# SCH_POC-HC-05_2022-12-13.net
KiCad netlist of a schematic drawn in EasyEDA
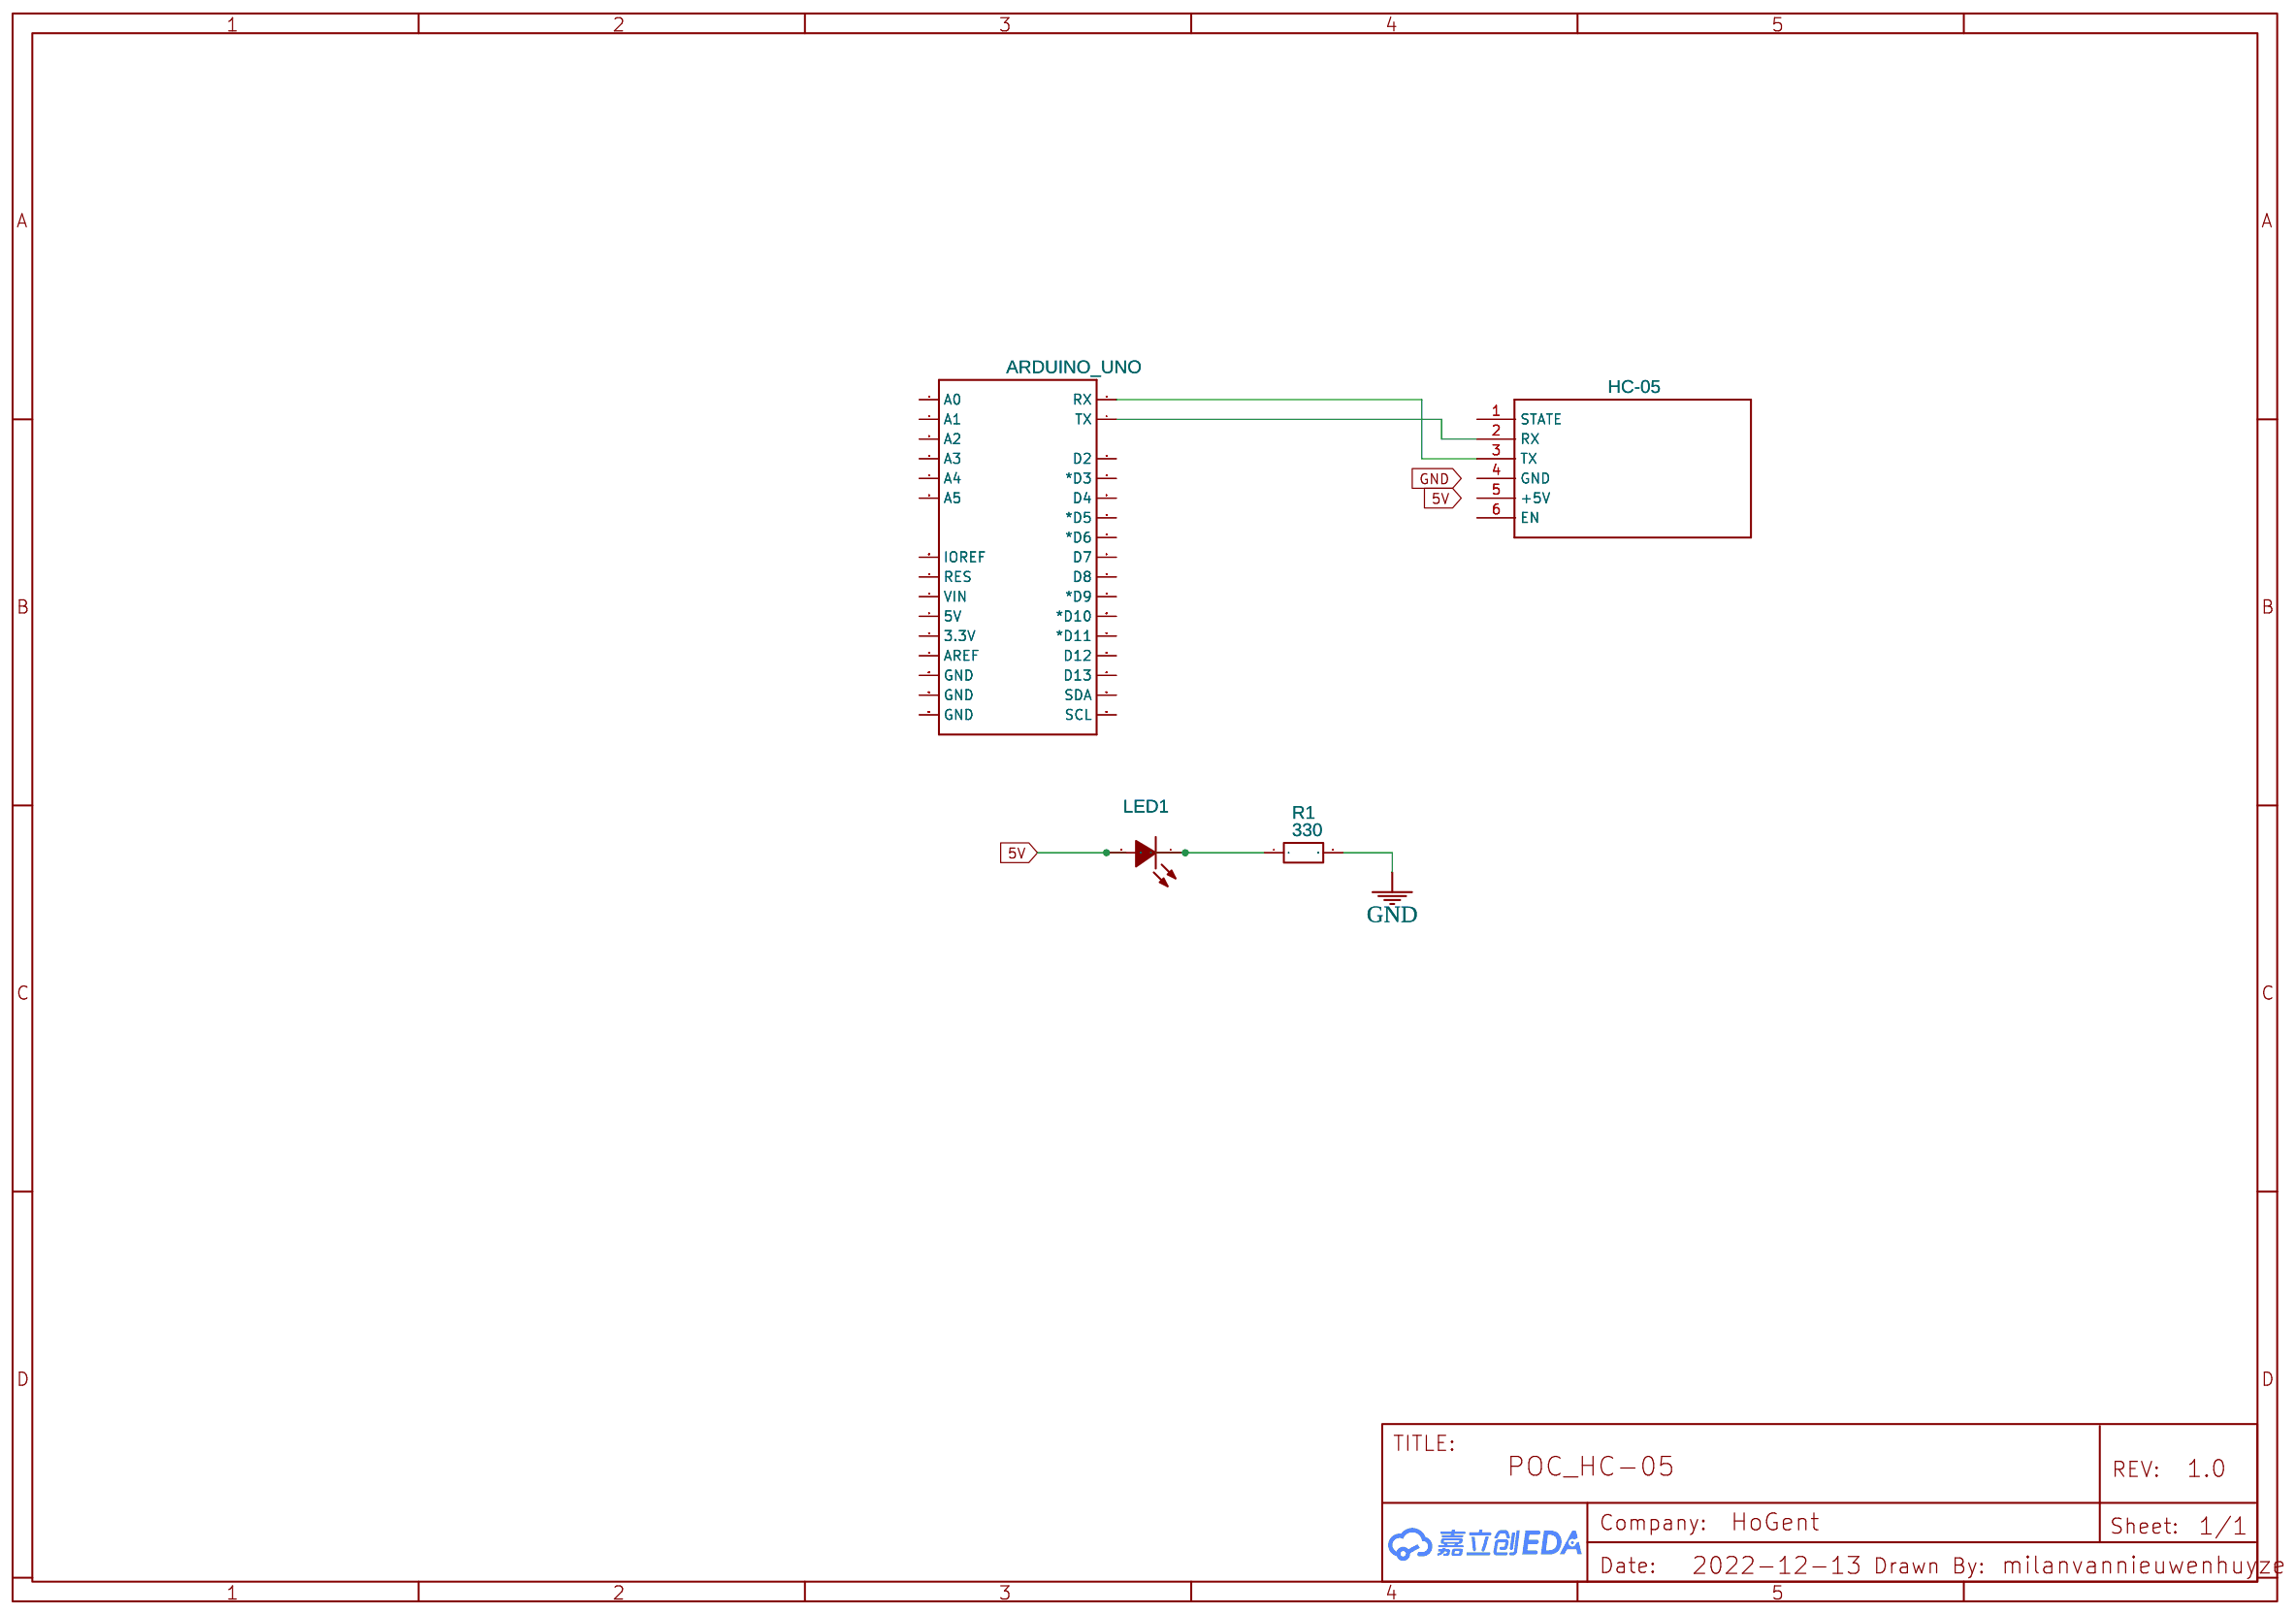
[diagram p0: schematic sheet]

(export (version "E")
  (design (tool "Eeschema 10.0.6"))
  (components
    (comp (ref "1") (value "HC-05") (libsource (lib "") (part "WIRELESS-BLUETOOTH-HC-05")))
    (comp (ref "LED1")
      (value "BL-HUE35A-AV-TRE")
      (fields (field (name "BOM_Supplier Part") "C138549"))
      (libsource (lib "") (part "BL-HUE35A-AV-TRE"))
    )
    (comp (ref "R1") (value "330") (libsource (lib "") (part "R_0603_EU")))
    (comp (ref "U1") (value "ARDUINO_UNO") (libsource (lib "") (part "ARDUINO_R3_SHIELD")))
  )
  (nets
    (net (code "1") (name "5V") (class "Default")
      (node (ref "LED1") (pin "2") (pinfunction "A_2") (pintype "unspecified"))
    )
    (net (code "2") (name "GND") (class "Default")
      (node (ref "R1") (pin "2") (pinfunction "2_2") (pintype "unspecified"))
    )
    (net (code "3") (name "Net-(1-RX)") (class "Default")
      (node (ref "1") (pin "2") (pinfunction "RX_2") (pintype "bidirectional"))
      (node (ref "U1") (pin "TX") (pinfunction "TX_TX") (pintype "unspecified"))
    )
    (net (code "4") (name "Net-(1-TX)") (class "Default")
      (node (ref "1") (pin "3") (pinfunction "TX_3") (pintype "bidirectional"))
      (node (ref "U1") (pin "RX") (pinfunction "RX_RX") (pintype "unspecified"))
    )
    (net (code "5") (name "Net-(LED1-K)") (class "Default")
      (node (ref "LED1") (pin "1") (pinfunction "K_1") (pintype "unspecified"))
      (node (ref "R1") (pin "1") (pinfunction "1_1") (pintype "unspecified"))
    )
    (net (code "6") (name "unconnected-(1-+5V-Pad5)") (class "Default")
      (node (ref "1") (pin "5") (pinfunction "+5V_5") (pintype "bidirectional"))
    )
    (net (code "7") (name "unconnected-(1-EN-Pad6)") (class "Default")
      (node (ref "1") (pin "6") (pinfunction "EN_6") (pintype "bidirectional"))
    )
    (net (code "8") (name "unconnected-(1-GND-Pad4)") (class "Default")
      (node (ref "1") (pin "4") (pinfunction "GND_4") (pintype "bidirectional"))
    )
    (net (code "9") (name "unconnected-(1-STATE-Pad1)") (class "Default")
      (node (ref "1") (pin "1") (pinfunction "STATE_1") (pintype "bidirectional"))
    )
    (net (code "10") (name "unconnected-(U1-*D3-PadD3)") (class "Default")
      (node (ref "U1") (pin "D3") (pinfunction "*D3_D3") (pintype "unspecified"))
    )
    (net (code "11") (name "unconnected-(U1-*D5-PadD5)") (class "Default")
      (node (ref "U1") (pin "D5") (pinfunction "*D5_D5") (pintype "unspecified"))
    )
    (net (code "12") (name "unconnected-(U1-*D6-PadD6)") (class "Default")
      (node (ref "U1") (pin "D6") (pinfunction "*D6_D6") (pintype "unspecified"))
    )
    (net (code "13") (name "unconnected-(U1-*D9-PadD9)") (class "Default")
      (node (ref "U1") (pin "D9") (pinfunction "*D9_D9") (pintype "unspecified"))
    )
    (net (code "14") (name "unconnected-(U1-*D10-PadD10)") (class "Default")
      (node (ref "U1") (pin "D10") (pinfunction "*D10_D10") (pintype "unspecified"))
    )
    (net (code "15") (name "unconnected-(U1-*D11-PadD11)") (class "Default")
      (node (ref "U1") (pin "D11") (pinfunction "*D11_D11") (pintype "unspecified"))
    )
    (net (code "16") (name "unconnected-(U1-GND-PadGND@0)") (class "Default")
      (node (ref "U1") (pin "GND@0") (pinfunction "GND_GND@0") (pintype "unspecified"))
    )
    (net (code "17") (name "unconnected-(U1-GND-PadGND@1)") (class "Default")
      (node (ref "U1") (pin "GND@1") (pinfunction "GND_GND@1") (pintype "unspecified"))
    )
    (net (code "18") (name "unconnected-(U1-GND-PadGND@2)") (class "Default")
      (node (ref "U1") (pin "GND@2") (pinfunction "GND_GND@2") (pintype "unspecified"))
    )
    (net (code "19") (name "unconnected-(U1-Pad3.3V)") (class "Default")
      (node (ref "U1") (pin "3.3V") (pinfunction "3.3V_3.3V") (pintype "unspecified"))
    )
    (net (code "20") (name "unconnected-(U1-Pad5V)") (class "Default")
      (node (ref "U1") (pin "5V") (pinfunction "5V_5V") (pintype "unspecified"))
    )
    (net (code "21") (name "unconnected-(U1-PadA0)") (class "Default")
      (node (ref "U1") (pin "A0") (pinfunction "A0_A0") (pintype "unspecified"))
    )
    (net (code "22") (name "unconnected-(U1-PadA1)") (class "Default")
      (node (ref "U1") (pin "A1") (pinfunction "A1_A1") (pintype "unspecified"))
    )
    (net (code "23") (name "unconnected-(U1-PadA2)") (class "Default")
      (node (ref "U1") (pin "A2") (pinfunction "A2_A2") (pintype "unspecified"))
    )
    (net (code "24") (name "unconnected-(U1-PadA3)") (class "Default")
      (node (ref "U1") (pin "A3") (pinfunction "A3_A3") (pintype "unspecified"))
    )
    (net (code "25") (name "unconnected-(U1-PadA4)") (class "Default")
      (node (ref "U1") (pin "A4") (pinfunction "A4_A4") (pintype "unspecified"))
    )
    (net (code "26") (name "unconnected-(U1-PadA5)") (class "Default")
      (node (ref "U1") (pin "A5") (pinfunction "A5_A5") (pintype "unspecified"))
    )
    (net (code "27") (name "unconnected-(U1-PadAREF)") (class "Default")
      (node (ref "U1") (pin "AREF") (pinfunction "AREF_AREF") (pintype "unspecified"))
    )
    (net (code "28") (name "unconnected-(U1-PadD2)") (class "Default")
      (node (ref "U1") (pin "D2") (pinfunction "D2_D2") (pintype "unspecified"))
    )
    (net (code "29") (name "unconnected-(U1-PadD4)") (class "Default")
      (node (ref "U1") (pin "D4") (pinfunction "D4_D4") (pintype "unspecified"))
    )
    (net (code "30") (name "unconnected-(U1-PadD7)") (class "Default")
      (node (ref "U1") (pin "D7") (pinfunction "D7_D7") (pintype "unspecified"))
    )
    (net (code "31") (name "unconnected-(U1-PadD8)") (class "Default")
      (node (ref "U1") (pin "D8") (pinfunction "D8_D8") (pintype "unspecified"))
    )
    (net (code "32") (name "unconnected-(U1-PadD12)") (class "Default")
      (node (ref "U1") (pin "D12") (pinfunction "D12_D12") (pintype "unspecified"))
    )
    (net (code "33") (name "unconnected-(U1-PadD13)") (class "Default")
      (node (ref "U1") (pin "D13") (pinfunction "D13_D13") (pintype "unspecified"))
    )
    (net (code "34") (name "unconnected-(U1-PadIOREF)") (class "Default")
      (node (ref "U1") (pin "IOREF") (pinfunction "IOREF_IOREF") (pintype "unspecified"))
    )
    (net (code "35") (name "unconnected-(U1-PadRES)") (class "Default")
      (node (ref "U1") (pin "RES") (pinfunction "RES_RES") (pintype "unspecified"))
    )
    (net (code "36") (name "unconnected-(U1-PadSCL)") (class "Default")
      (node (ref "U1") (pin "SCL") (pinfunction "SCL_SCL") (pintype "unspecified"))
    )
    (net (code "37") (name "unconnected-(U1-PadSDA)") (class "Default")
      (node (ref "U1") (pin "SDA") (pinfunction "SDA_SDA") (pintype "unspecified"))
    )
    (net (code "38") (name "unconnected-(U1-PadVIN)") (class "Default")
      (node (ref "U1") (pin "VIN") (pinfunction "VIN_VIN") (pintype "unspecified"))
    )
  )
)
